# rs485_sisaku.net
KiCad netlist of a schematic drawn in EAGLE
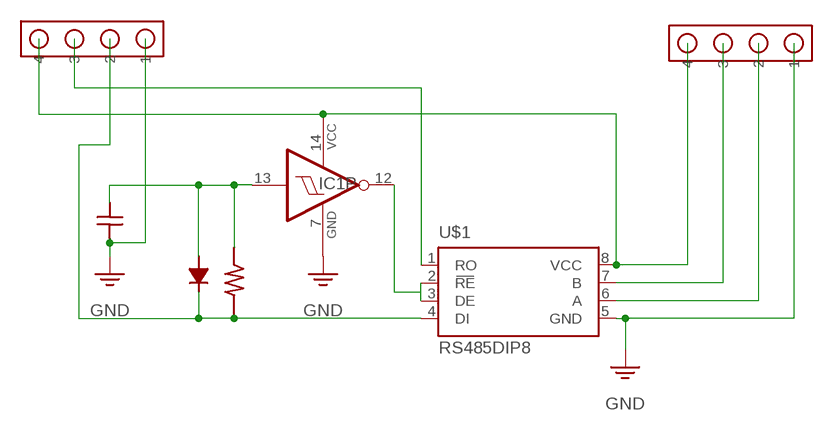
[diagram p0: schematic, sheet 1]

(export (version "E")
  (design (tool "Eeschema 10.0.6"))
  (components
    (comp (ref "IC1")
      (value "7414N")
      (footprint "eagle-import:DIL14")
      (libsource (lib "eagle-import") (part "7414N"))
    )
    (comp (ref "U$1")
      (value "RS485DIP8")
      (footprint "eagle-import:DIP826W53P254L959H508Q8B")
      (libsource (lib "eagle-import") (part "RS485DIP8"))
    )
    (comp (ref "U$2")
      (value "RESISTOR")
      (footprint "eagle-import:RESISTOR-1_4W")
      (libsource (lib "eagle-import") (part "RESISTOR"))
    )
    (comp (ref "U$3")
      (value "DIODE-S")
      (footprint "eagle-import:DIODE-S")
      (libsource (lib "eagle-import") (part "DIODE-S"))
    )
    (comp (ref "U$5")
      (value "CAPACITOR-CEL")
      (footprint "eagle-import:100NF")
      (libsource (lib "eagle-import") (part "CAPACITOR-CEL"))
    )
    (comp (ref "U$8")
      (value "EH4")
      (footprint "eagle-import:EH4")
      (libsource (lib "eagle-import") (part "EH4"))
    )
    (comp (ref "U$9")
      (value "EH4")
      (footprint "eagle-import:EH4")
      (libsource (lib "eagle-import") (part "EH4"))
    )
  )
  (nets
    (net (code "1") (name "GND") (class "Default")
      (node (ref "IC1") (pin "7") (pinfunction "GND_7") (pintype "power_in"))
      (node (ref "U$1") (pin "5") (pinfunction "GND_5") (pintype "bidirectional"))
      (node (ref "U$5") (pin "1") (pinfunction "1_1") (pintype "bidirectional"))
      (node (ref "U$8") (pin "1") (pinfunction "1_1") (pintype "bidirectional"))
      (node (ref "U$9") (pin "1") (pinfunction "1_1") (pintype "bidirectional"))
    )
    (net (code "2") (name "Net-(IC1A-I)") (class "Default")
      (node (ref "IC1") (pin "13") (pinfunction "I_13") (pintype "input"))
      (node (ref "U$2") (pin "P$2") (pinfunction "P$2_P$2") (pintype "bidirectional"))
      (node (ref "U$3") (pin "1") (pinfunction "1_1") (pintype "bidirectional"))
      (node (ref "U$5") (pin "2") (pinfunction "2_2") (pintype "bidirectional"))
    )
    (net (code "3") (name "Net-(IC1A-O)") (class "Default")
      (node (ref "IC1") (pin "12") (pinfunction "O_12") (pintype "output"))
      (node (ref "U$1") (pin "2") (pinfunction "RE_2") (pintype "bidirectional"))
      (node (ref "U$1") (pin "3") (pinfunction "DE_3") (pintype "bidirectional"))
    )
    (net (code "4") (name "Net-(IC1G-VCC)") (class "Default")
      (node (ref "IC1") (pin "14") (pinfunction "VCC_14") (pintype "power_in"))
      (node (ref "U$1") (pin "8") (pinfunction "VCC_8") (pintype "bidirectional"))
      (node (ref "U$8") (pin "4") (pinfunction "4_4") (pintype "bidirectional"))
      (node (ref "U$9") (pin "4") (pinfunction "4_4") (pintype "bidirectional"))
    )
    (net (code "5") (name "Net-(U$1-A)") (class "Default")
      (node (ref "U$1") (pin "6") (pinfunction "A_6") (pintype "bidirectional"))
      (node (ref "U$9") (pin "2") (pinfunction "2_2") (pintype "bidirectional"))
    )
    (net (code "6") (name "Net-(U$1-B)") (class "Default")
      (node (ref "U$1") (pin "7") (pinfunction "B_7") (pintype "bidirectional"))
      (node (ref "U$9") (pin "3") (pinfunction "3_3") (pintype "bidirectional"))
    )
    (net (code "7") (name "Net-(U$1-DI)") (class "Default")
      (node (ref "U$1") (pin "4") (pinfunction "DI_4") (pintype "bidirectional"))
      (node (ref "U$2") (pin "P$1") (pinfunction "P$1_P$1") (pintype "bidirectional"))
      (node (ref "U$3") (pin "2") (pinfunction "2_2") (pintype "bidirectional"))
      (node (ref "U$8") (pin "2") (pinfunction "2_2") (pintype "bidirectional"))
    )
    (net (code "8") (name "Net-(U$1-RO)") (class "Default")
      (node (ref "U$1") (pin "1") (pinfunction "RO_1") (pintype "bidirectional"))
      (node (ref "U$8") (pin "3") (pinfunction "3_3") (pintype "bidirectional"))
    )
  )
)
